# bekono2.net
KiCad netlist of a schematic drawn in EAGLE
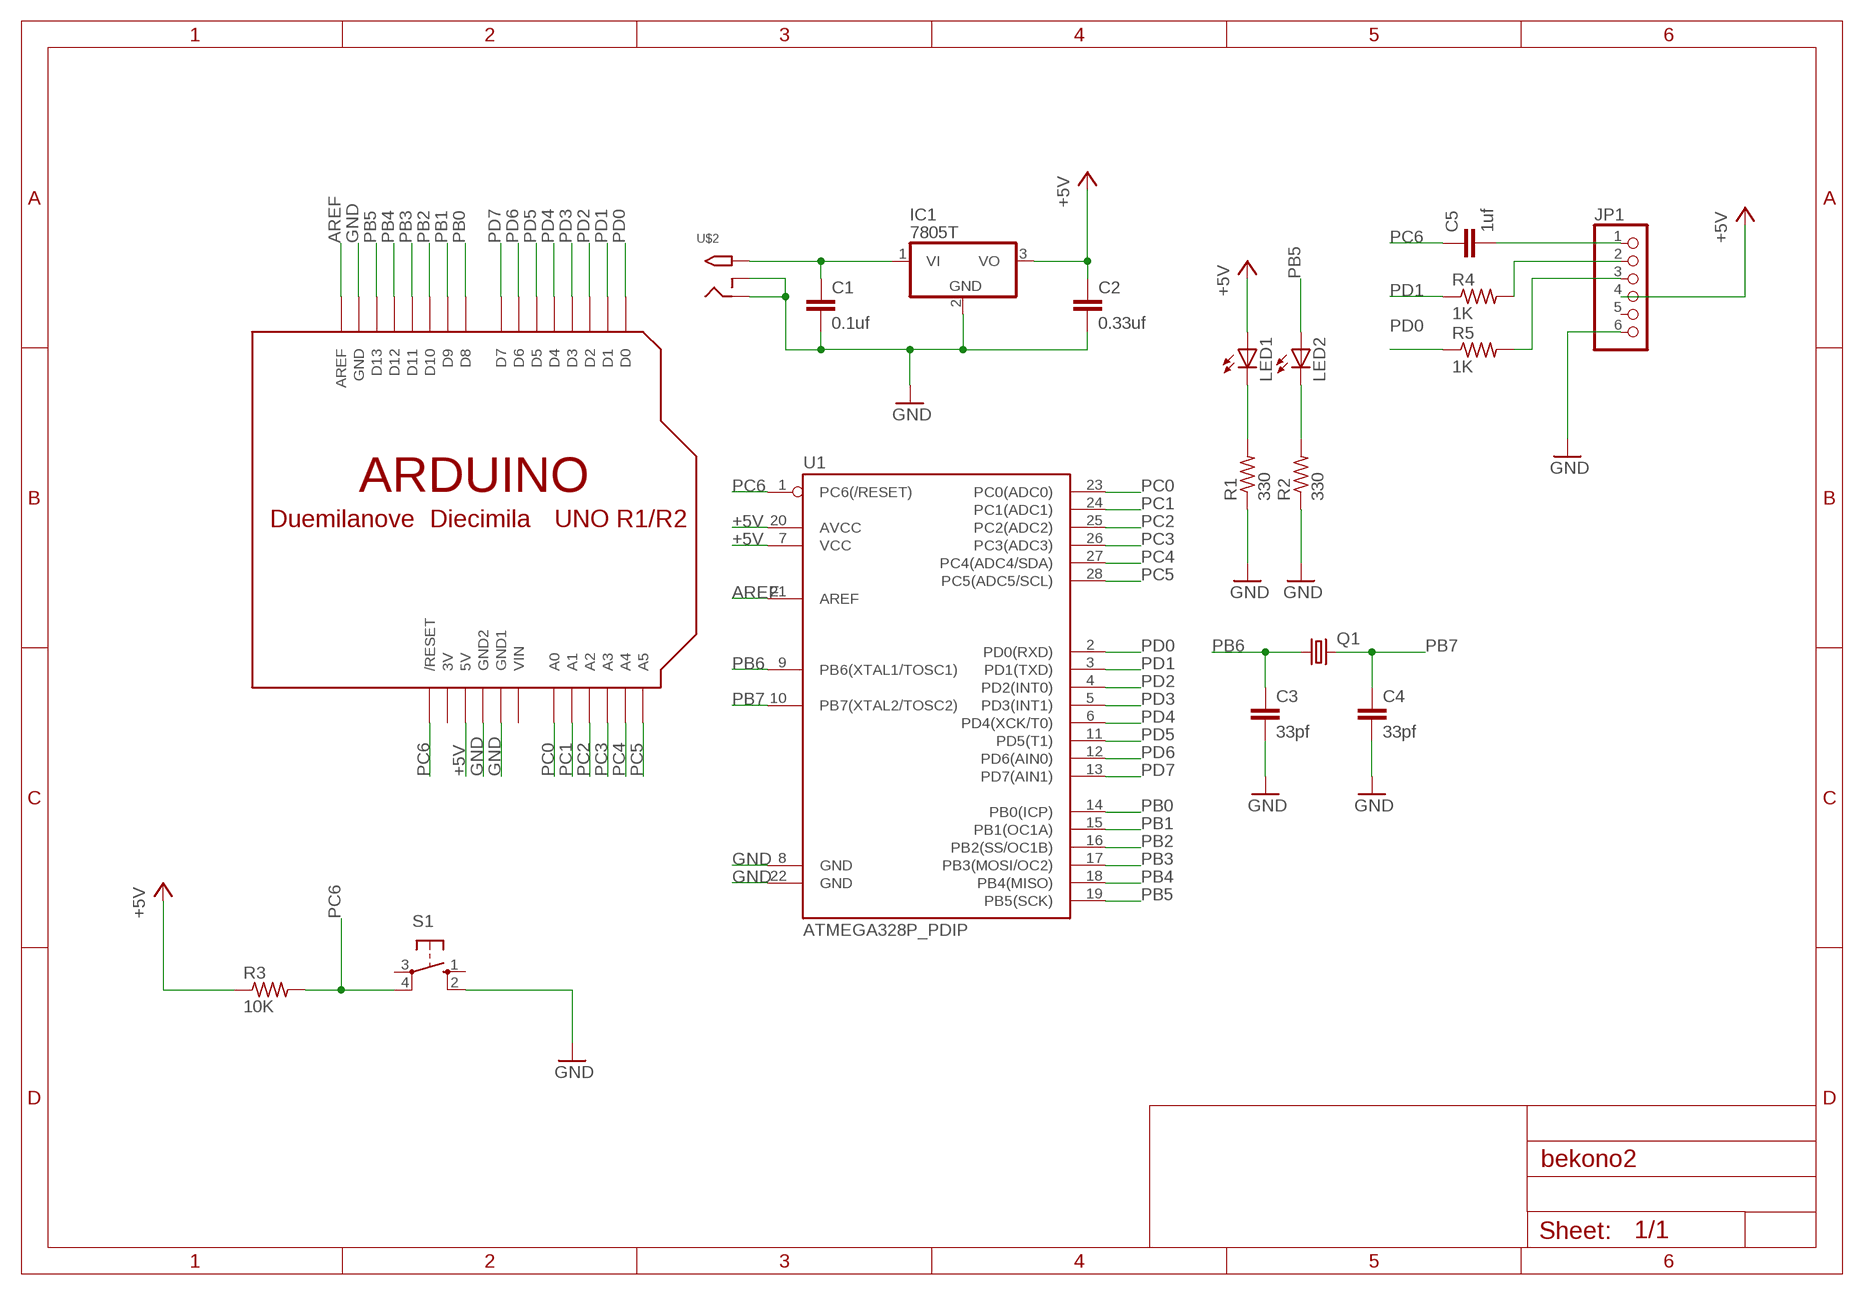
[diagram p0: schematic, sheet 1]

(export (version "E")
  (design (tool "Eeschema 10.0.6"))
  (components
    (comp (ref "C1")
      (value "0.1uf")
      (footprint "eagle-import:C2.5-2")
      (libsource (lib "eagle-import") (part "C2.5/2"))
    )
    (comp (ref "C2")
      (value "0.33uf")
      (footprint "eagle-import:C2.5-2")
      (libsource (lib "eagle-import") (part "C2.5/2"))
    )
    (comp (ref "C3")
      (value "33pf")
      (footprint "eagle-import:C2.5-2")
      (libsource (lib "eagle-import") (part "C2.5/2"))
    )
    (comp (ref "C4")
      (value "33pf")
      (footprint "eagle-import:C2.5-2")
      (libsource (lib "eagle-import") (part "C2.5/2"))
    )
    (comp (ref "C5")
      (value "1uf")
      (footprint "eagle-import:C2.5-2")
      (libsource (lib "eagle-import") (part "C2.5/2"))
    )
    (comp (ref "IC1")
      (value "7805T")
      (footprint "eagle-import:TO220H")
      (libsource (lib "eagle-import") (part "78T05"))
    )
    (comp (ref "JP1")
      (value "PINHD-1X6CB")
      (footprint "eagle-import:1X06-CLEANBIG")
      (libsource (lib "eagle-import") (part "PINHD-1X6CB"))
    )
    (comp (ref "LED1")
      (value "LED5MM")
      (footprint "eagle-import:LED5MM")
      (libsource (lib "eagle-import") (part "LED5MM"))
    )
    (comp (ref "LED2")
      (value "LED5MM")
      (footprint "eagle-import:LED5MM")
      (libsource (lib "eagle-import") (part "LED5MM"))
    )
    (comp (ref "Q1")
      (value "CRYSTALHC49S")
      (footprint "eagle-import:HC49_S")
      (libsource (lib "eagle-import") (part "CRYSTALHC49S"))
    )
    (comp (ref "R1")
      (value "330")
      (footprint "eagle-import:0805-THM")
      (libsource (lib "eagle-import") (part "FLIPFLOP-RES"))
    )
    (comp (ref "R2")
      (value "330")
      (footprint "eagle-import:0805-THM")
      (libsource (lib "eagle-import") (part "FLIPFLOP-RES"))
    )
    (comp (ref "R3")
      (value "10K")
      (footprint "eagle-import:0805-THM")
      (libsource (lib "eagle-import") (part "FLIPFLOP-RES"))
    )
    (comp (ref "R4")
      (value "1K")
      (footprint "eagle-import:0805-THM")
      (libsource (lib "eagle-import") (part "FLIPFLOP-RES"))
    )
    (comp (ref "R5")
      (value "1K")
      (footprint "eagle-import:0805-THM")
      (libsource (lib "eagle-import") (part "FLIPFLOP-RES"))
    )
    (comp (ref "S1")
      (value "10-XX")
      (footprint "eagle-import:B3F-10XX")
      (fields (field (name "MPN") "B3F-1000"))
      (libsource (lib "eagle-import") (part "10-XX"))
    )
    (comp (ref "U$1")
      (value "ARDUINO-BPLACE")
      (footprint "eagle-import:ARDUINO-BPLACE")
      (libsource (lib "eagle-import") (part "ARDUINO-BPLACE"))
    )
    (comp (ref "U$2")
      (value "2.1MMJACKTHM")
      (footprint "eagle-import:PJ-102A")
      (libsource (lib "eagle-import") (part "2.1MMJACKTHM"))
    )
    (comp (ref "U1")
      (value "ATMEGA328P_PDIP")
      (footprint "eagle-import:DIL28-3")
      (libsource (lib "eagle-import") (part "ATMEGA328P_PDIP"))
    )
  )
  (nets
    (net (code "1") (name "+5V") (class "Default")
      (node (ref "C2") (pin "1") (pinfunction "1_1") (pintype "passive"))
      (node (ref "IC1") (pin "3") (pinfunction "VO_3") (pintype "passive"))
      (node (ref "JP1") (pin "4") (pinfunction "4_4") (pintype "passive"))
      (node (ref "LED1") (pin "A") (pinfunction "A_A") (pintype "passive"))
      (node (ref "R3") (pin "1") (pinfunction "1_1") (pintype "passive"))
      (node (ref "U$1") (pin "5V") (pinfunction "5V_5V") (pintype "power_in"))
      (node (ref "U1") (pin "20") (pinfunction "AVCC_20") (pintype "bidirectional"))
      (node (ref "U1") (pin "7") (pinfunction "VCC_7") (pintype "bidirectional"))
    )
    (net (code "2") (name "/3V") (class "Default")
      (node (ref "U$1") (pin "3V") (pinfunction "3V_3V") (pintype "power_in"))
    )
    (net (code "3") (name "/AREF") (class "Default")
      (node (ref "U$1") (pin "AREF") (pinfunction "AREF_AREF") (pintype "bidirectional"))
      (node (ref "U1") (pin "21") (pinfunction "AREF_21") (pintype "bidirectional"))
    )
    (net (code "4") (name "/PB0") (class "Default")
      (node (ref "U$1") (pin "D8") (pinfunction "D8_D8") (pintype "bidirectional"))
      (node (ref "U1") (pin "14") (pinfunction "PB0(ICP)_14") (pintype "bidirectional"))
    )
    (net (code "5") (name "/PB1") (class "Default")
      (node (ref "U$1") (pin "D9") (pinfunction "D9_D9") (pintype "bidirectional"))
      (node (ref "U1") (pin "15") (pinfunction "PB1(OC1A)_15") (pintype "bidirectional"))
    )
    (net (code "6") (name "/PB2") (class "Default")
      (node (ref "U$1") (pin "D10") (pinfunction "D10_D10") (pintype "bidirectional"))
      (node (ref "U1") (pin "16") (pinfunction "PB2(SS/OC1B)_16") (pintype "bidirectional"))
    )
    (net (code "7") (name "/PB3") (class "Default")
      (node (ref "U$1") (pin "D11") (pinfunction "D11_D11") (pintype "bidirectional"))
      (node (ref "U1") (pin "17") (pinfunction "PB3(MOSI/OC2)_17") (pintype "bidirectional"))
    )
    (net (code "8") (name "/PB4") (class "Default")
      (node (ref "U$1") (pin "D12") (pinfunction "D12_D12") (pintype "bidirectional"))
      (node (ref "U1") (pin "18") (pinfunction "PB4(MISO)_18") (pintype "bidirectional"))
    )
    (net (code "9") (name "/PB5") (class "Default")
      (node (ref "LED2") (pin "A") (pinfunction "A_A") (pintype "passive"))
      (node (ref "U$1") (pin "D13") (pinfunction "D13_D13") (pintype "bidirectional"))
      (node (ref "U1") (pin "19") (pinfunction "PB5(SCK)_19") (pintype "bidirectional"))
    )
    (net (code "10") (name "/PB6") (class "Default")
      (node (ref "C3") (pin "1") (pinfunction "1_1") (pintype "passive"))
      (node (ref "Q1") (pin "1") (pinfunction "1_1") (pintype "passive"))
      (node (ref "U1") (pin "9") (pinfunction "PB6(XTAL1/TOSC1)_9") (pintype "bidirectional"))
    )
    (net (code "11") (name "/PB7") (class "Default")
      (node (ref "C4") (pin "1") (pinfunction "1_1") (pintype "passive"))
      (node (ref "Q1") (pin "2") (pinfunction "2_2") (pintype "passive"))
      (node (ref "U1") (pin "10") (pinfunction "PB7(XTAL2/TOSC2)_10") (pintype "bidirectional"))
    )
    (net (code "12") (name "/PC0") (class "Default")
      (node (ref "U$1") (pin "A0") (pinfunction "A0_A0") (pintype "bidirectional"))
      (node (ref "U1") (pin "23") (pinfunction "PC0(ADC0)_23") (pintype "bidirectional"))
    )
    (net (code "13") (name "/PC1") (class "Default")
      (node (ref "U$1") (pin "A1") (pinfunction "A1_A1") (pintype "bidirectional"))
      (node (ref "U1") (pin "24") (pinfunction "PC1(ADC1)_24") (pintype "bidirectional"))
    )
    (net (code "14") (name "/PC2") (class "Default")
      (node (ref "U$1") (pin "A2") (pinfunction "A2_A2") (pintype "bidirectional"))
      (node (ref "U1") (pin "25") (pinfunction "PC2(ADC2)_25") (pintype "bidirectional"))
    )
    (net (code "15") (name "/PC3") (class "Default")
      (node (ref "U$1") (pin "A3") (pinfunction "A3_A3") (pintype "bidirectional"))
      (node (ref "U1") (pin "26") (pinfunction "PC3(ADC3)_26") (pintype "bidirectional"))
    )
    (net (code "16") (name "/PC4") (class "Default")
      (node (ref "U$1") (pin "A4") (pinfunction "A4_A4") (pintype "bidirectional"))
      (node (ref "U1") (pin "27") (pinfunction "PC4(ADC4/SDA)_27") (pintype "bidirectional"))
    )
    (net (code "17") (name "/PC5") (class "Default")
      (node (ref "U$1") (pin "A5") (pinfunction "A5_A5") (pintype "bidirectional"))
      (node (ref "U1") (pin "28") (pinfunction "PC5(ADC5/SCL)_28") (pintype "bidirectional"))
    )
    (net (code "18") (name "/PC6") (class "Default")
      (node (ref "C5") (pin "1") (pinfunction "1_1") (pintype "passive"))
      (node (ref "R3") (pin "2") (pinfunction "2_2") (pintype "passive"))
      (node (ref "S1") (pin "4") (pinfunction "P1_4") (pintype "passive"))
      (node (ref "U$1") (pin "RESET") (pinfunction "/RESET_RESET") (pintype "bidirectional"))
      (node (ref "U1") (pin "1") (pinfunction "PC6(/RESET)_1") (pintype "bidirectional"))
    )
    (net (code "19") (name "/PD0") (class "Default")
      (node (ref "R5") (pin "1") (pinfunction "1_1") (pintype "passive"))
      (node (ref "U$1") (pin "D0") (pinfunction "D0_D0") (pintype "bidirectional"))
      (node (ref "U1") (pin "2") (pinfunction "PD0(RXD)_2") (pintype "bidirectional"))
    )
    (net (code "20") (name "/PD1") (class "Default")
      (node (ref "R4") (pin "1") (pinfunction "1_1") (pintype "passive"))
      (node (ref "U$1") (pin "D1") (pinfunction "D1_D1") (pintype "bidirectional"))
      (node (ref "U1") (pin "3") (pinfunction "PD1(TXD)_3") (pintype "bidirectional"))
    )
    (net (code "21") (name "/PD2") (class "Default")
      (node (ref "U$1") (pin "D2") (pinfunction "D2_D2") (pintype "bidirectional"))
      (node (ref "U1") (pin "4") (pinfunction "PD2(INT0)_4") (pintype "bidirectional"))
    )
    (net (code "22") (name "/PD3") (class "Default")
      (node (ref "U$1") (pin "D3") (pinfunction "D3_D3") (pintype "bidirectional"))
      (node (ref "U1") (pin "5") (pinfunction "PD3(INT1)_5") (pintype "bidirectional"))
    )
    (net (code "23") (name "/PD4") (class "Default")
      (node (ref "U$1") (pin "D4") (pinfunction "D4_D4") (pintype "bidirectional"))
      (node (ref "U1") (pin "6") (pinfunction "PD4(XCK/T0)_6") (pintype "bidirectional"))
    )
    (net (code "24") (name "/PD5") (class "Default")
      (node (ref "U$1") (pin "D5") (pinfunction "D5_D5") (pintype "bidirectional"))
      (node (ref "U1") (pin "11") (pinfunction "PD5(T1)_11") (pintype "bidirectional"))
    )
    (net (code "25") (name "/PD6") (class "Default")
      (node (ref "U$1") (pin "D6") (pinfunction "D6_D6") (pintype "bidirectional"))
      (node (ref "U1") (pin "12") (pinfunction "PD6(AIN0)_12") (pintype "bidirectional"))
    )
    (net (code "26") (name "/PD7") (class "Default")
      (node (ref "U$1") (pin "D7") (pinfunction "D7_D7") (pintype "bidirectional"))
      (node (ref "U1") (pin "13") (pinfunction "PD7(AIN1)_13") (pintype "bidirectional"))
    )
    (net (code "27") (name "/VIN") (class "Default")
      (node (ref "U$1") (pin "VIN") (pinfunction "VIN_VIN") (pintype "power_in"))
    )
    (net (code "28") (name "GND") (class "Default")
      (node (ref "C1") (pin "2") (pinfunction "2_2") (pintype "passive"))
      (node (ref "C2") (pin "2") (pinfunction "2_2") (pintype "passive"))
      (node (ref "C3") (pin "2") (pinfunction "2_2") (pintype "passive"))
      (node (ref "C4") (pin "2") (pinfunction "2_2") (pintype "passive"))
      (node (ref "IC1") (pin "2") (pinfunction "GND_2") (pintype "passive"))
      (node (ref "JP1") (pin "6") (pinfunction "6_6") (pintype "passive"))
      (node (ref "R1") (pin "1") (pinfunction "1_1") (pintype "passive"))
      (node (ref "R2") (pin "1") (pinfunction "1_1") (pintype "passive"))
      (node (ref "S1") (pin "2") (pinfunction "S1_2") (pintype "passive"))
      (node (ref "U$1") (pin "GND") (pinfunction "GND_GND") (pintype "power_in"))
      (node (ref "U$1") (pin "GND1") (pinfunction "GND1_GND1") (pintype "power_in"))
      (node (ref "U$1") (pin "GND2") (pinfunction "GND2_GND2") (pintype "power_in"))
      (node (ref "U$2") (pin "RING") (pinfunction "RING_RING") (pintype "bidirectional"))
      (node (ref "U$2") (pin "RING_SW") (pinfunction "RING_SW_RING_SW") (pintype "bidirectional"))
      (node (ref "U1") (pin "22") (pinfunction "GND_22") (pintype "bidirectional"))
      (node (ref "U1") (pin "8") (pinfunction "GND_8") (pintype "bidirectional"))
    )
    (net (code "29") (name "Net-(C5-Pad2)") (class "Default")
      (node (ref "C5") (pin "2") (pinfunction "2_2") (pintype "passive"))
      (node (ref "JP1") (pin "1") (pinfunction "1_1") (pintype "passive"))
    )
    (net (code "30") (name "Net-(IC1-VI)") (class "Default")
      (node (ref "C1") (pin "1") (pinfunction "1_1") (pintype "passive"))
      (node (ref "IC1") (pin "1") (pinfunction "VI_1") (pintype "input"))
      (node (ref "U$2") (pin "TIP") (pinfunction "TIP_TIP") (pintype "bidirectional"))
    )
    (net (code "31") (name "Net-(JP1-Pad2)") (class "Default")
      (node (ref "JP1") (pin "2") (pinfunction "2_2") (pintype "passive"))
      (node (ref "R4") (pin "2") (pinfunction "2_2") (pintype "passive"))
    )
    (net (code "32") (name "Net-(JP1-Pad3)") (class "Default")
      (node (ref "JP1") (pin "3") (pinfunction "3_3") (pintype "passive"))
      (node (ref "R5") (pin "2") (pinfunction "2_2") (pintype "passive"))
    )
    (net (code "33") (name "Net-(LED1-C)") (class "Default")
      (node (ref "LED1") (pin "K") (pinfunction "C_K") (pintype "passive"))
      (node (ref "R1") (pin "2") (pinfunction "2_2") (pintype "passive"))
    )
    (net (code "34") (name "Net-(LED2-C)") (class "Default")
      (node (ref "LED2") (pin "K") (pinfunction "C_K") (pintype "passive"))
      (node (ref "R2") (pin "2") (pinfunction "2_2") (pintype "passive"))
    )
    (net (code "35") (name "unconnected-(JP1-Pad5)") (class "Default")
      (node (ref "JP1") (pin "5") (pinfunction "5_5") (pintype "passive"))
    )
    (net (code "36") (name "unconnected-(S1-P-Pad3)") (class "Default")
      (node (ref "S1") (pin "3") (pinfunction "P_3") (pintype "passive"))
    )
    (net (code "37") (name "unconnected-(S1-S-Pad1)") (class "Default")
      (node (ref "S1") (pin "1") (pinfunction "S_1") (pintype "passive"))
    )
  )
)
